# stm32hw05.net
KiCad netlist of a schematic drawn in EAGLE
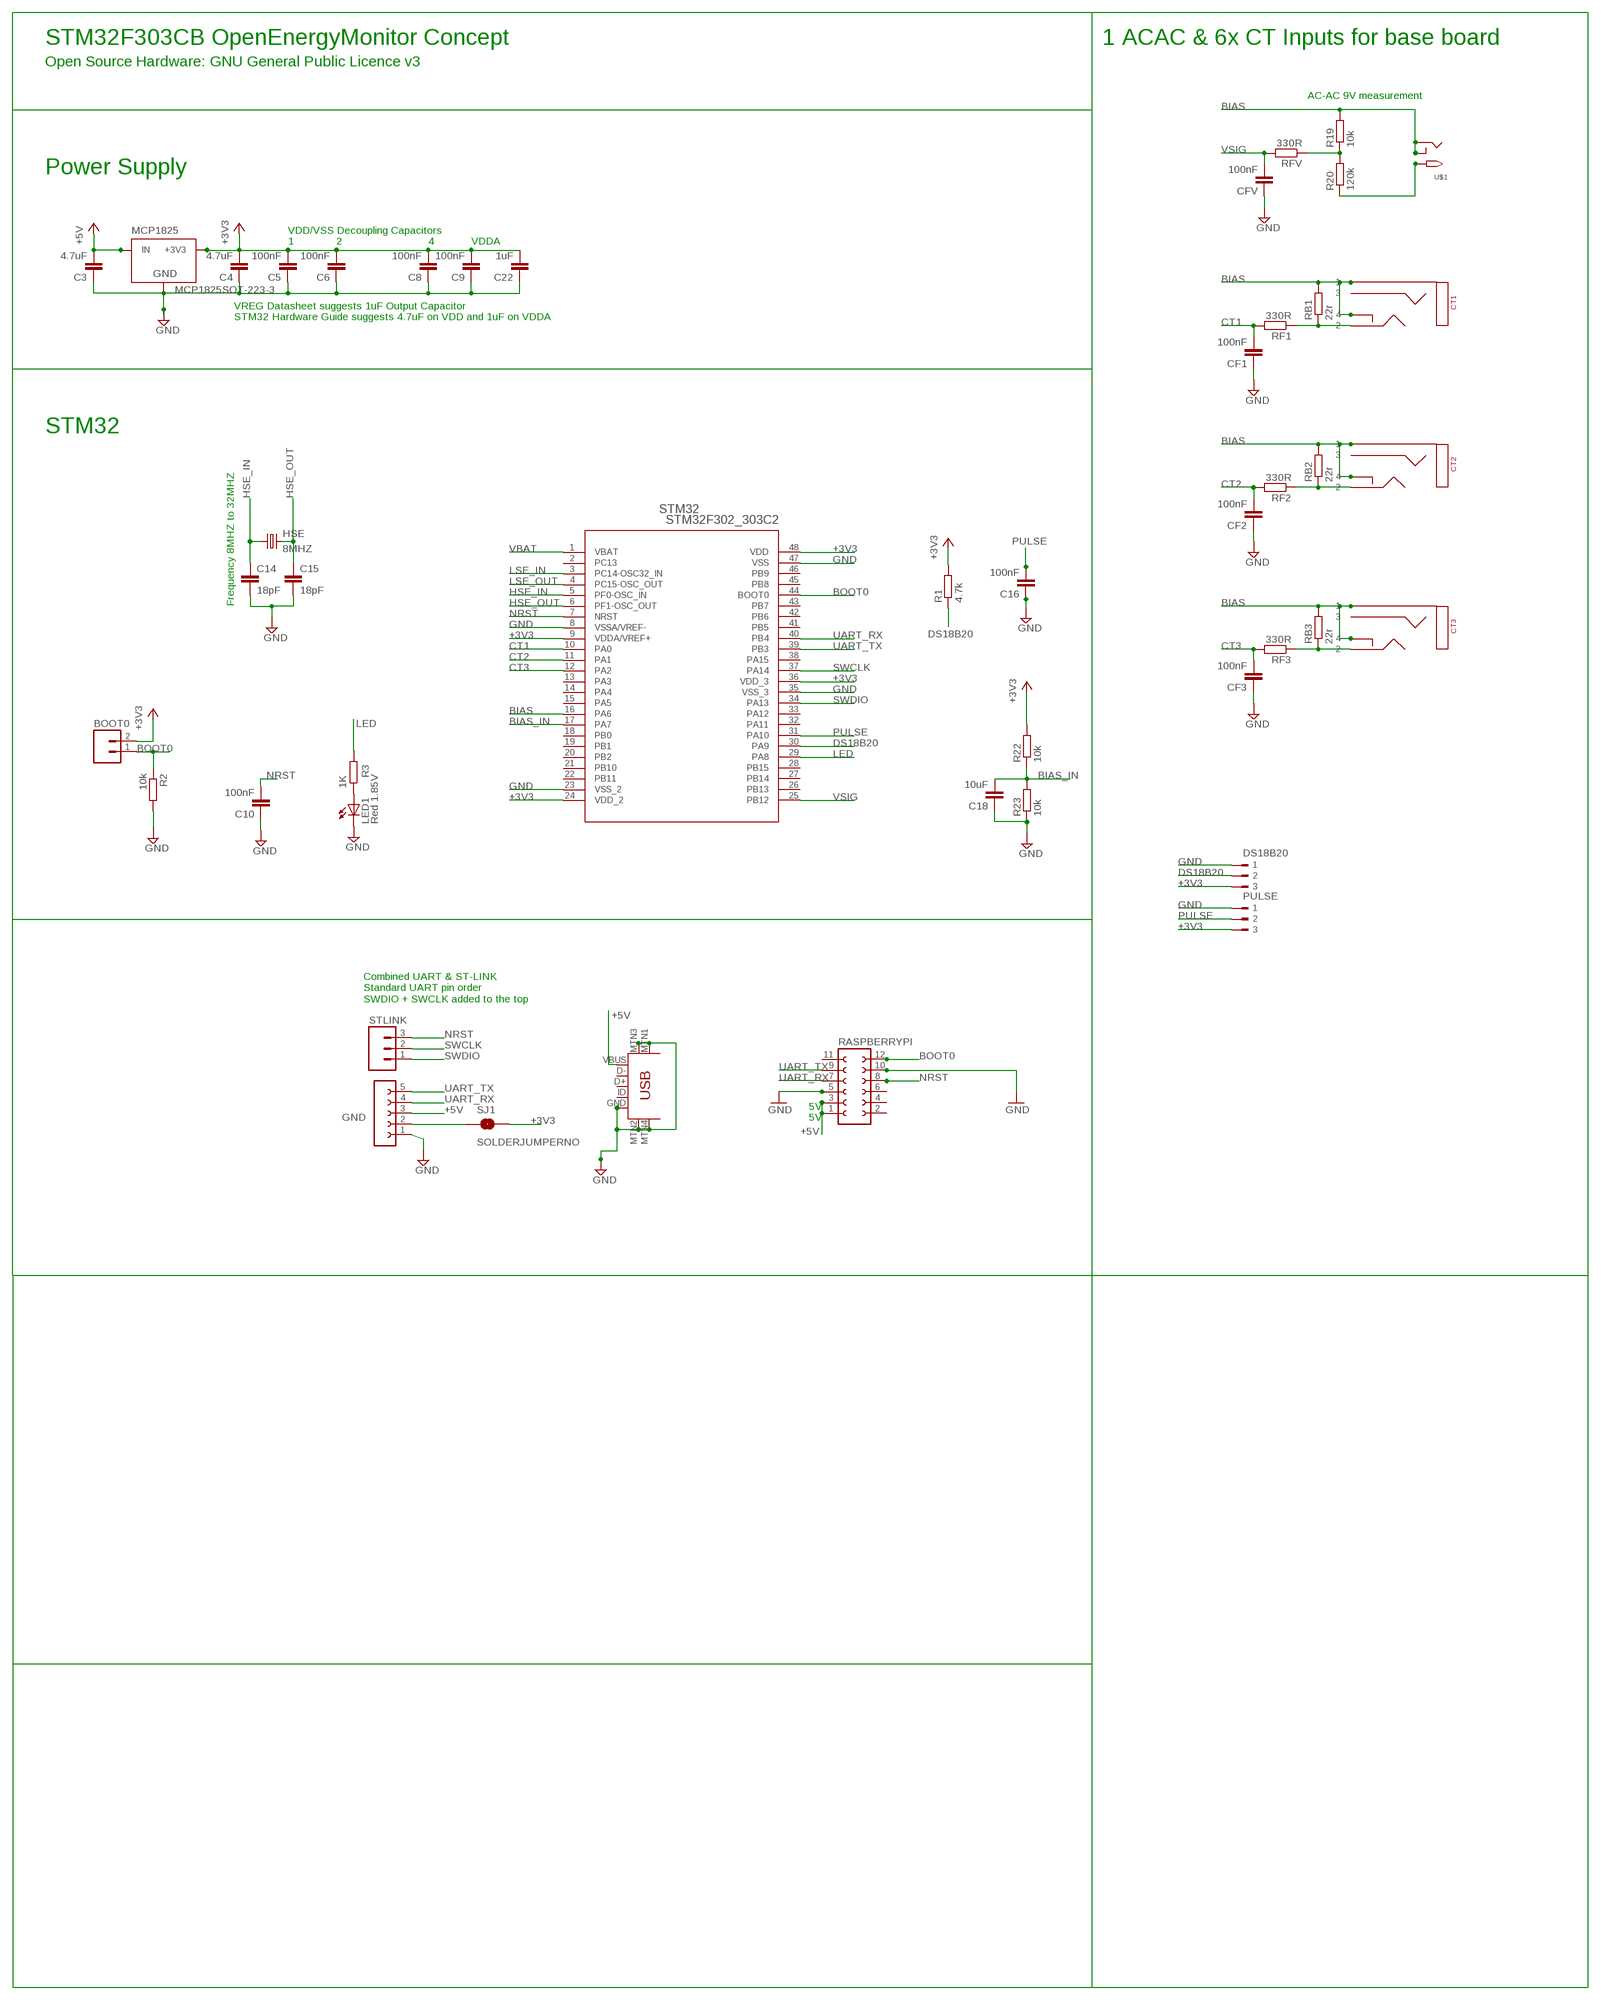
[diagram p0: schematic, sheet 1]

(export (version "E")
  (design (tool "Eeschema 10.0.6"))
  (components
    (comp (ref "BOOT0")
      (value "M02PTH")
      (footprint "eagle-import:1X02")
      (libsource (lib "eagle-import") (part "M02PTH"))
    )
    (comp (ref "C3")
      (value "4.7uF")
      (footprint "eagle-import:C0603")
      (libsource (lib "eagle-import") (part "C-EUC0603"))
    )
    (comp (ref "C4")
      (value "4.7uF")
      (footprint "eagle-import:C0603")
      (libsource (lib "eagle-import") (part "C-EUC0603"))
    )
    (comp (ref "C5")
      (value "100nF")
      (footprint "eagle-import:C0603")
      (libsource (lib "eagle-import") (part "C-EUC0603"))
    )
    (comp (ref "C6")
      (value "100nF")
      (footprint "eagle-import:C0603")
      (libsource (lib "eagle-import") (part "C-EUC0603"))
    )
    (comp (ref "C8")
      (value "100nF")
      (footprint "eagle-import:C0603")
      (libsource (lib "eagle-import") (part "C-EUC0603"))
    )
    (comp (ref "C9")
      (value "100nF")
      (footprint "eagle-import:C0603")
      (libsource (lib "eagle-import") (part "C-EUC0603"))
    )
    (comp (ref "C10")
      (value "100nF")
      (footprint "eagle-import:C0603")
      (libsource (lib "eagle-import") (part "C-EUC0603"))
    )
    (comp (ref "C14")
      (value "18pF")
      (footprint "eagle-import:C0603")
      (libsource (lib "eagle-import") (part "C-EUC0603"))
    )
    (comp (ref "C15")
      (value "18pF")
      (footprint "eagle-import:C0603")
      (libsource (lib "eagle-import") (part "C-EUC0603"))
    )
    (comp (ref "C16")
      (value "100nF")
      (footprint "eagle-import:C0603")
      (libsource (lib "eagle-import") (part "C-EUC0603"))
    )
    (comp (ref "C18")
      (value "10uF")
      (footprint "eagle-import:C0603")
      (libsource (lib "eagle-import") (part "C-EUC0603"))
    )
    (comp (ref "C22")
      (value "1uF")
      (footprint "eagle-import:C0603")
      (libsource (lib "eagle-import") (part "C-EUC0603"))
    )
    (comp (ref "CF1")
      (value "100nF")
      (footprint "eagle-import:C0603")
      (libsource (lib "eagle-import") (part "C-EUC0603"))
    )
    (comp (ref "CF2")
      (value "100nF")
      (footprint "eagle-import:C0603")
      (libsource (lib "eagle-import") (part "C-EUC0603"))
    )
    (comp (ref "CF3")
      (value "100nF")
      (footprint "eagle-import:C0603")
      (libsource (lib "eagle-import") (part "C-EUC0603"))
    )
    (comp (ref "CFV")
      (value "100nF")
      (footprint "eagle-import:C0603")
      (libsource (lib "eagle-import") (part "C-EUC0603"))
    )
    (comp (ref "CT1")
      (value "STEREO_SMD")
      (footprint "eagle-import:STEREO_SMT")
      (libsource (lib "eagle-import") (part "STEREO_SMD"))
    )
    (comp (ref "CT2")
      (value "STEREO_SMD")
      (footprint "eagle-import:STEREO_SMT")
      (libsource (lib "eagle-import") (part "STEREO_SMD"))
    )
    (comp (ref "CT3")
      (value "STEREO_SMD")
      (footprint "eagle-import:STEREO_SMT")
      (libsource (lib "eagle-import") (part "STEREO_SMD"))
    )
    (comp (ref "DS18B20")
      (value "180-3")
      (footprint "eagle-import:180-3")
      (libsource (lib "eagle-import") (part "180-3"))
    )
    (comp (ref "GND")
      (value "UART")
      (footprint "eagle-import:FE05-1")
      (libsource (lib "eagle-import") (part "FE05-1"))
    )
    (comp (ref "HSE")
      (value "8MHZ")
      (footprint "eagle-import:CTS406")
      (libsource (lib "eagle-import") (part "CRYSTALCTS406"))
    )
    (comp (ref "LED1")
      (value "Red 1.85V")
      (footprint "eagle-import:CHIP-LED0805")
      (libsource (lib "eagle-import") (part "LEDCHIP-LED0805"))
    )
    (comp (ref "MCP1825")
      (value "MCP1825SOT-223-3")
      (footprint "eagle-import:SOT-223")
      (libsource (lib "eagle-import") (part "MCP1825SOT-223-3"))
    )
    (comp (ref "PULSE")
      (value "180-3")
      (footprint "eagle-import:180-3")
      (libsource (lib "eagle-import") (part "180-3"))
    )
    (comp (ref "R1")
      (value "4.7k")
      (footprint "eagle-import:R0603")
      (libsource (lib "eagle-import") (part "resistor_R-EU_R0603"))
    )
    (comp (ref "R2")
      (value "10k")
      (footprint "eagle-import:R0603")
      (libsource (lib "eagle-import") (part "resistor_R-EU_R0603"))
    )
    (comp (ref "R3")
      (value "1K")
      (footprint "eagle-import:R0603")
      (libsource (lib "eagle-import") (part "R-EU_R0603"))
    )
    (comp (ref "R19")
      (value "10k")
      (footprint "eagle-import:R0603")
      (libsource (lib "eagle-import") (part "resistor_R-EU_R0603"))
    )
    (comp (ref "R20")
      (value "120k")
      (footprint "eagle-import:R0603")
      (libsource (lib "eagle-import") (part "resistor_R-EU_R0603"))
    )
    (comp (ref "R22")
      (value "10k")
      (footprint "eagle-import:R0603")
      (libsource (lib "eagle-import") (part "resistor_R-EU_R0603"))
    )
    (comp (ref "R23")
      (value "10k")
      (footprint "eagle-import:R0603")
      (libsource (lib "eagle-import") (part "resistor_R-EU_R0603"))
    )
    (comp (ref "RASPBERRYPI")
      (value "FE06-2")
      (footprint "eagle-import:FE06-2")
      (libsource (lib "eagle-import") (part "FE06-2"))
    )
    (comp (ref "RB1")
      (value "22r")
      (footprint "eagle-import:R0603")
      (libsource (lib "eagle-import") (part "resistor_R-EU_R0603"))
    )
    (comp (ref "RB2")
      (value "22r")
      (footprint "eagle-import:R0603")
      (libsource (lib "eagle-import") (part "resistor_R-EU_R0603"))
    )
    (comp (ref "RB3")
      (value "22r")
      (footprint "eagle-import:R0603")
      (libsource (lib "eagle-import") (part "resistor_R-EU_R0603"))
    )
    (comp (ref "RF1")
      (value "330R")
      (footprint "eagle-import:R0603")
      (libsource (lib "eagle-import") (part "resistor_R-EU_R0603"))
    )
    (comp (ref "RF2")
      (value "330R")
      (footprint "eagle-import:R0603")
      (libsource (lib "eagle-import") (part "resistor_R-EU_R0603"))
    )
    (comp (ref "RF3")
      (value "330R")
      (footprint "eagle-import:R0603")
      (libsource (lib "eagle-import") (part "resistor_R-EU_R0603"))
    )
    (comp (ref "RFV")
      (value "330R")
      (footprint "eagle-import:R0603")
      (libsource (lib "eagle-import") (part "resistor_R-EU_R0603"))
    )
    (comp (ref "SJ1")
      (value "SOLDERJUMPERNO")
      (footprint "eagle-import:SJ_2S-NO")
      (libsource (lib "eagle-import") (part "SOLDERJUMPERNO"))
    )
    (comp (ref "STLINK")
      (value "M03PTH")
      (footprint "eagle-import:1X03")
      (libsource (lib "eagle-import") (part "M03PTH"))
    )
    (comp (ref "STM32")
      (value "STM32F302_303C2")
      (footprint "eagle-import:LQFP48-7X7MM")
      (fields (field (name "MANUFACTURER_PART_NUMBER") "stm32f302_303c2"))
      (libsource (lib "eagle-import") (part "STM32F302_303C2"))
    )
    (comp (ref "U$1")
      (value "2.1MMJACKSMT")
      (footprint "eagle-import:DCJACK_2MM_SMT")
      (libsource (lib "eagle-import") (part "2.1MMJACKSMT"))
    )
    (comp (ref "U$10")
      (value "USB-MINIB-5PIN")
      (footprint "eagle-import:USB-MINIB-CISECO")
      (libsource (lib "eagle-import") (part "USB-MINIB-5PIN"))
    )
  )
  (nets
    (net (code "1") (name "+3V3") (class "Default")
      (node (ref "BOOT0") (pin "2") (pinfunction "2_2") (pintype "passive"))
      (node (ref "C22") (pin "2") (pinfunction "2_2") (pintype "passive"))
      (node (ref "C4") (pin "2") (pinfunction "2_2") (pintype "passive"))
      (node (ref "C5") (pin "2") (pinfunction "2_2") (pintype "passive"))
      (node (ref "C6") (pin "2") (pinfunction "2_2") (pintype "passive"))
      (node (ref "C8") (pin "2") (pinfunction "2_2") (pintype "passive"))
      (node (ref "C9") (pin "2") (pinfunction "2_2") (pintype "passive"))
      (node (ref "DS18B20") (pin "3") (pinfunction "3_3") (pintype "passive"))
      (node (ref "MCP1825") (pin "3") (pinfunction "+3V3_3") (pintype "power_in"))
      (node (ref "PULSE") (pin "3") (pinfunction "3_3") (pintype "passive"))
      (node (ref "R1") (pin "2") (pinfunction "2_2") (pintype "passive"))
      (node (ref "R22") (pin "2") (pinfunction "2_2") (pintype "passive"))
      (node (ref "SJ1") (pin "2") (pinfunction "2_2") (pintype "passive"))
      (node (ref "STM32") (pin "24") (pinfunction "VDD_2_24") (pintype "power_in"))
      (node (ref "STM32") (pin "36") (pinfunction "VDD_3_36") (pintype "power_in"))
      (node (ref "STM32") (pin "48") (pinfunction "VDD_48") (pintype "power_in"))
      (node (ref "STM32") (pin "9") (pinfunction "VDDA/VREF+_9") (pintype "power_in"))
    )
    (net (code "2") (name "+5V") (class "Default")
      (node (ref "C3") (pin "2") (pinfunction "2_2") (pintype "passive"))
      (node (ref "GND") (pin "3") (pinfunction "3_3") (pintype "passive"))
      (node (ref "MCP1825") (pin "1") (pinfunction "IN_1") (pintype "power_in"))
      (node (ref "RASPBERRYPI") (pin "1") (pinfunction "1_1") (pintype "passive"))
      (node (ref "RASPBERRYPI") (pin "3") (pinfunction "3_3") (pintype "passive"))
      (node (ref "U$10") (pin "VBUS") (pinfunction "VBUS_VBUS") (pintype "bidirectional"))
    )
    (net (code "3") (name "/BIAS") (class "Default")
      (node (ref "CT1") (pin "P$1") (pinfunction "1_P$1") (pintype "bidirectional"))
      (node (ref "CT1") (pin "P$4") (pinfunction "4_P$4") (pintype "bidirectional"))
      (node (ref "CT2") (pin "P$1") (pinfunction "1_P$1") (pintype "bidirectional"))
      (node (ref "CT2") (pin "P$4") (pinfunction "4_P$4") (pintype "bidirectional"))
      (node (ref "CT3") (pin "P$1") (pinfunction "1_P$1") (pintype "bidirectional"))
      (node (ref "CT3") (pin "P$4") (pinfunction "4_P$4") (pintype "bidirectional"))
      (node (ref "R19") (pin "2") (pinfunction "2_2") (pintype "passive"))
      (node (ref "RB1") (pin "2") (pinfunction "2_2") (pintype "passive"))
      (node (ref "RB2") (pin "2") (pinfunction "2_2") (pintype "passive"))
      (node (ref "RB3") (pin "2") (pinfunction "2_2") (pintype "passive"))
      (node (ref "STM32") (pin "16") (pinfunction "PA6_16") (pintype "bidirectional"))
      (node (ref "U$1") (pin "GND") (pinfunction "RING_GND") (pintype "bidirectional"))
      (node (ref "U$1") (pin "GNDBREAK") (pinfunction "RING_SW_GNDBREAK") (pintype "bidirectional"))
    )
    (net (code "4") (name "/BIAS_IN") (class "Default")
      (node (ref "C18") (pin "2") (pinfunction "2_2") (pintype "passive"))
      (node (ref "R22") (pin "1") (pinfunction "1_1") (pintype "passive"))
      (node (ref "R23") (pin "2") (pinfunction "2_2") (pintype "passive"))
      (node (ref "STM32") (pin "17") (pinfunction "PA7_17") (pintype "bidirectional"))
    )
    (net (code "5") (name "/BOOT0") (class "Default")
      (node (ref "BOOT0") (pin "1") (pinfunction "1_1") (pintype "passive"))
      (node (ref "R2") (pin "1") (pinfunction "1_1") (pintype "passive"))
      (node (ref "RASPBERRYPI") (pin "12") (pinfunction "12_12") (pintype "passive"))
      (node (ref "STM32") (pin "44") (pinfunction "BOOT0_44") (pintype "input"))
    )
    (net (code "6") (name "/CT1") (class "Default")
      (node (ref "CF1") (pin "2") (pinfunction "2_2") (pintype "passive"))
      (node (ref "RF1") (pin "2") (pinfunction "2_2") (pintype "passive"))
      (node (ref "STM32") (pin "10") (pinfunction "PA0_10") (pintype "bidirectional"))
    )
    (net (code "7") (name "/CT2") (class "Default")
      (node (ref "CF2") (pin "2") (pinfunction "2_2") (pintype "passive"))
      (node (ref "RF2") (pin "2") (pinfunction "2_2") (pintype "passive"))
      (node (ref "STM32") (pin "11") (pinfunction "PA1_11") (pintype "bidirectional"))
    )
    (net (code "8") (name "/CT3") (class "Default")
      (node (ref "CF3") (pin "2") (pinfunction "2_2") (pintype "passive"))
      (node (ref "RF3") (pin "2") (pinfunction "2_2") (pintype "passive"))
      (node (ref "STM32") (pin "12") (pinfunction "PA2_12") (pintype "bidirectional"))
    )
    (net (code "9") (name "/DS18B20") (class "Default")
      (node (ref "DS18B20") (pin "2") (pinfunction "2_2") (pintype "passive"))
      (node (ref "R1") (pin "1") (pinfunction "1_1") (pintype "passive"))
      (node (ref "STM32") (pin "30") (pinfunction "PA9_30") (pintype "bidirectional"))
    )
    (net (code "10") (name "/HSE_IN") (class "Default")
      (node (ref "C14") (pin "1") (pinfunction "1_1") (pintype "passive"))
      (node (ref "HSE") (pin "1") (pinfunction "1_1") (pintype "passive"))
      (node (ref "STM32") (pin "5") (pinfunction "PF0-OSC_IN_5") (pintype "bidirectional"))
    )
    (net (code "11") (name "/HSE_OUT") (class "Default")
      (node (ref "C15") (pin "1") (pinfunction "1_1") (pintype "passive"))
      (node (ref "HSE") (pin "3") (pinfunction "2_3") (pintype "passive"))
      (node (ref "STM32") (pin "6") (pinfunction "PF1-OSC_OUT_6") (pintype "bidirectional"))
    )
    (net (code "12") (name "/LED") (class "Default")
      (node (ref "R3") (pin "2") (pinfunction "2_2") (pintype "passive"))
      (node (ref "STM32") (pin "29") (pinfunction "PA8_29") (pintype "bidirectional"))
    )
    (net (code "13") (name "/LSE_IN") (class "Default")
      (node (ref "STM32") (pin "3") (pinfunction "PC14-OSC32_IN_3") (pintype "bidirectional"))
    )
    (net (code "14") (name "/LSE_OUT") (class "Default")
      (node (ref "STM32") (pin "4") (pinfunction "PC15-OSC_OUT_4") (pintype "bidirectional"))
    )
    (net (code "15") (name "/NRST") (class "Default")
      (node (ref "C10") (pin "2") (pinfunction "2_2") (pintype "passive"))
      (node (ref "RASPBERRYPI") (pin "8") (pinfunction "8_8") (pintype "passive"))
      (node (ref "STLINK") (pin "3") (pinfunction "3_3") (pintype "passive"))
      (node (ref "STM32") (pin "7") (pinfunction "NRST_7") (pintype "bidirectional"))
    )
    (net (code "16") (name "/PULSE") (class "Default")
      (node (ref "C16") (pin "2") (pinfunction "2_2") (pintype "passive"))
      (node (ref "PULSE") (pin "2") (pinfunction "2_2") (pintype "passive"))
      (node (ref "STM32") (pin "31") (pinfunction "PA10_31") (pintype "bidirectional"))
    )
    (net (code "17") (name "/SWCLK") (class "Default")
      (node (ref "STLINK") (pin "2") (pinfunction "2_2") (pintype "passive"))
      (node (ref "STM32") (pin "37") (pinfunction "PA14_37") (pintype "bidirectional"))
    )
    (net (code "18") (name "/SWDIO") (class "Default")
      (node (ref "STLINK") (pin "1") (pinfunction "1_1") (pintype "passive"))
      (node (ref "STM32") (pin "34") (pinfunction "PA13_34") (pintype "bidirectional"))
    )
    (net (code "19") (name "/UART_RX") (class "Default")
      (node (ref "GND") (pin "4") (pinfunction "4_4") (pintype "passive"))
      (node (ref "RASPBERRYPI") (pin "7") (pinfunction "7_7") (pintype "passive"))
      (node (ref "STM32") (pin "40") (pinfunction "PB4_40") (pintype "bidirectional"))
    )
    (net (code "20") (name "/UART_TX") (class "Default")
      (node (ref "GND") (pin "5") (pinfunction "5_5") (pintype "passive"))
      (node (ref "RASPBERRYPI") (pin "9") (pinfunction "9_9") (pintype "passive"))
      (node (ref "STM32") (pin "39") (pinfunction "PB3_39") (pintype "bidirectional"))
    )
    (net (code "21") (name "/VBAT") (class "Default")
      (node (ref "STM32") (pin "1") (pinfunction "VBAT_1") (pintype "power_in"))
    )
    (net (code "22") (name "/VSIG") (class "Default")
      (node (ref "CFV") (pin "2") (pinfunction "2_2") (pintype "passive"))
      (node (ref "RFV") (pin "2") (pinfunction "2_2") (pintype "passive"))
      (node (ref "STM32") (pin "25") (pinfunction "PB12_25") (pintype "bidirectional"))
    )
    (net (code "23") (name "GND") (class "Default")
      (node (ref "C10") (pin "1") (pinfunction "1_1") (pintype "passive"))
      (node (ref "C14") (pin "2") (pinfunction "2_2") (pintype "passive"))
      (node (ref "C15") (pin "2") (pinfunction "2_2") (pintype "passive"))
      (node (ref "C16") (pin "1") (pinfunction "1_1") (pintype "passive"))
      (node (ref "C18") (pin "1") (pinfunction "1_1") (pintype "passive"))
      (node (ref "C22") (pin "1") (pinfunction "1_1") (pintype "passive"))
      (node (ref "C3") (pin "1") (pinfunction "1_1") (pintype "passive"))
      (node (ref "C4") (pin "1") (pinfunction "1_1") (pintype "passive"))
      (node (ref "C5") (pin "1") (pinfunction "1_1") (pintype "passive"))
      (node (ref "C6") (pin "1") (pinfunction "1_1") (pintype "passive"))
      (node (ref "C8") (pin "1") (pinfunction "1_1") (pintype "passive"))
      (node (ref "C9") (pin "1") (pinfunction "1_1") (pintype "passive"))
      (node (ref "CF1") (pin "1") (pinfunction "1_1") (pintype "passive"))
      (node (ref "CF2") (pin "1") (pinfunction "1_1") (pintype "passive"))
      (node (ref "CF3") (pin "1") (pinfunction "1_1") (pintype "passive"))
      (node (ref "CFV") (pin "1") (pinfunction "1_1") (pintype "passive"))
      (node (ref "DS18B20") (pin "1") (pinfunction "1_1") (pintype "passive"))
      (node (ref "GND") (pin "1") (pinfunction "1_1") (pintype "passive"))
      (node (ref "LED1") (pin "C") (pinfunction "C_C") (pintype "passive"))
      (node (ref "MCP1825") (pin "2") (pinfunction "GND_2") (pintype "power_in"))
      (node (ref "PULSE") (pin "1") (pinfunction "1_1") (pintype "passive"))
      (node (ref "R2") (pin "2") (pinfunction "2_2") (pintype "passive"))
      (node (ref "R23") (pin "1") (pinfunction "1_1") (pintype "passive"))
      (node (ref "RASPBERRYPI") (pin "10") (pinfunction "10_10") (pintype "passive"))
      (node (ref "RASPBERRYPI") (pin "5") (pinfunction "5_5") (pintype "passive"))
      (node (ref "STM32") (pin "23") (pinfunction "VSS_2_23") (pintype "power_in"))
      (node (ref "STM32") (pin "35") (pinfunction "VSS_3_35") (pintype "power_in"))
      (node (ref "STM32") (pin "47") (pinfunction "VSS_47") (pintype "power_in"))
      (node (ref "STM32") (pin "8") (pinfunction "VSSA/VREF-_8") (pintype "power_in"))
      (node (ref "U$10") (pin "GND") (pinfunction "GND_GND") (pintype "bidirectional"))
      (node (ref "U$10") (pin "MTN1") (pinfunction "MTN2_MTN1") (pintype "bidirectional"))
      (node (ref "U$10") (pin "MTN2") (pinfunction "MTN3_MTN2") (pintype "bidirectional"))
      (node (ref "U$10") (pin "MTN3") (pinfunction "MTN1_MTN3") (pintype "bidirectional"))
      (node (ref "U$10") (pin "MTN4") (pinfunction "MTN4_MTN4") (pintype "bidirectional"))
    )
    (net (code "24") (name "Net-(CT1-2)") (class "Default")
      (node (ref "CT1") (pin "P$2") (pinfunction "2_P$2") (pintype "bidirectional"))
      (node (ref "RB1") (pin "1") (pinfunction "1_1") (pintype "passive"))
      (node (ref "RF1") (pin "1") (pinfunction "1_1") (pintype "passive"))
    )
    (net (code "25") (name "Net-(CT2-2)") (class "Default")
      (node (ref "CT2") (pin "P$2") (pinfunction "2_P$2") (pintype "bidirectional"))
      (node (ref "RB2") (pin "1") (pinfunction "1_1") (pintype "passive"))
      (node (ref "RF2") (pin "1") (pinfunction "1_1") (pintype "passive"))
    )
    (net (code "26") (name "Net-(CT3-2)") (class "Default")
      (node (ref "CT3") (pin "P$2") (pinfunction "2_P$2") (pintype "bidirectional"))
      (node (ref "RB3") (pin "1") (pinfunction "1_1") (pintype "passive"))
      (node (ref "RF3") (pin "1") (pinfunction "1_1") (pintype "passive"))
    )
    (net (code "27") (name "Net-(GND-Pad2)") (class "Default")
      (node (ref "GND") (pin "2") (pinfunction "2_2") (pintype "passive"))
      (node (ref "SJ1") (pin "1") (pinfunction "1_1") (pintype "passive"))
    )
    (net (code "28") (name "Net-(LED1-PadA)") (class "Default")
      (node (ref "LED1") (pin "A") (pinfunction "A_A") (pintype "passive"))
      (node (ref "R3") (pin "1") (pinfunction "1_1") (pintype "passive"))
    )
    (net (code "29") (name "Net-(R19-Pad1)") (class "Default")
      (node (ref "R19") (pin "1") (pinfunction "1_1") (pintype "passive"))
      (node (ref "R20") (pin "2") (pinfunction "2_2") (pintype "passive"))
      (node (ref "RFV") (pin "1") (pinfunction "1_1") (pintype "passive"))
    )
    (net (code "30") (name "Net-(U$1-TIP)") (class "Default")
      (node (ref "R20") (pin "1") (pinfunction "1_1") (pintype "passive"))
      (node (ref "U$1") (pin "PWR2") (pinfunction "TIP_PWR2") (pintype "bidirectional"))
    )
    (net (code "31") (name "unconnected-(CT1-3-PadP$3)") (class "Default")
      (node (ref "CT1") (pin "P$3") (pinfunction "3_P$3") (pintype "bidirectional"))
    )
    (net (code "32") (name "unconnected-(CT2-3-PadP$3)") (class "Default")
      (node (ref "CT2") (pin "P$3") (pinfunction "3_P$3") (pintype "bidirectional"))
    )
    (net (code "33") (name "unconnected-(CT3-3-PadP$3)") (class "Default")
      (node (ref "CT3") (pin "P$3") (pinfunction "3_P$3") (pintype "bidirectional"))
    )
    (net (code "34") (name "unconnected-(RASPBERRYPI-Pad2)") (class "Default")
      (node (ref "RASPBERRYPI") (pin "2") (pinfunction "2_2") (pintype "passive"))
    )
    (net (code "35") (name "unconnected-(RASPBERRYPI-Pad4)") (class "Default")
      (node (ref "RASPBERRYPI") (pin "4") (pinfunction "4_4") (pintype "passive"))
    )
    (net (code "36") (name "unconnected-(RASPBERRYPI-Pad6)") (class "Default")
      (node (ref "RASPBERRYPI") (pin "6") (pinfunction "6_6") (pintype "passive"))
    )
    (net (code "37") (name "unconnected-(RASPBERRYPI-Pad11)") (class "Default")
      (node (ref "RASPBERRYPI") (pin "11") (pinfunction "11_11") (pintype "passive"))
    )
    (net (code "38") (name "unconnected-(STM32-PA3-Pad13)") (class "Default")
      (node (ref "STM32") (pin "13") (pinfunction "PA3_13") (pintype "bidirectional"))
    )
    (net (code "39") (name "unconnected-(STM32-PA4-Pad14)") (class "Default")
      (node (ref "STM32") (pin "14") (pinfunction "PA4_14") (pintype "bidirectional"))
    )
    (net (code "40") (name "unconnected-(STM32-PA5-Pad15)") (class "Default")
      (node (ref "STM32") (pin "15") (pinfunction "PA5_15") (pintype "bidirectional"))
    )
    (net (code "41") (name "unconnected-(STM32-PA11-Pad32)") (class "Default")
      (node (ref "STM32") (pin "32") (pinfunction "PA11_32") (pintype "bidirectional"))
    )
    (net (code "42") (name "unconnected-(STM32-PA12-Pad33)") (class "Default")
      (node (ref "STM32") (pin "33") (pinfunction "PA12_33") (pintype "bidirectional"))
    )
    (net (code "43") (name "unconnected-(STM32-PA15-Pad38)") (class "Default")
      (node (ref "STM32") (pin "38") (pinfunction "PA15_38") (pintype "bidirectional"))
    )
    (net (code "44") (name "unconnected-(STM32-PB0-Pad18)") (class "Default")
      (node (ref "STM32") (pin "18") (pinfunction "PB0_18") (pintype "bidirectional"))
    )
    (net (code "45") (name "unconnected-(STM32-PB1-Pad19)") (class "Default")
      (node (ref "STM32") (pin "19") (pinfunction "PB1_19") (pintype "bidirectional"))
    )
    (net (code "46") (name "unconnected-(STM32-PB2-Pad20)") (class "Default")
      (node (ref "STM32") (pin "20") (pinfunction "PB2_20") (pintype "bidirectional"))
    )
    (net (code "47") (name "unconnected-(STM32-PB5-Pad41)") (class "Default")
      (node (ref "STM32") (pin "41") (pinfunction "PB5_41") (pintype "bidirectional"))
    )
    (net (code "48") (name "unconnected-(STM32-PB6-Pad42)") (class "Default")
      (node (ref "STM32") (pin "42") (pinfunction "PB6_42") (pintype "bidirectional"))
    )
    (net (code "49") (name "unconnected-(STM32-PB7-Pad43)") (class "Default")
      (node (ref "STM32") (pin "43") (pinfunction "PB7_43") (pintype "bidirectional"))
    )
    (net (code "50") (name "unconnected-(STM32-PB8-Pad45)") (class "Default")
      (node (ref "STM32") (pin "45") (pinfunction "PB8_45") (pintype "bidirectional"))
    )
    (net (code "51") (name "unconnected-(STM32-PB9-Pad46)") (class "Default")
      (node (ref "STM32") (pin "46") (pinfunction "PB9_46") (pintype "bidirectional"))
    )
    (net (code "52") (name "unconnected-(STM32-PB10-Pad21)") (class "Default")
      (node (ref "STM32") (pin "21") (pinfunction "PB10_21") (pintype "bidirectional"))
    )
    (net (code "53") (name "unconnected-(STM32-PB11-Pad22)") (class "Default")
      (node (ref "STM32") (pin "22") (pinfunction "PB11_22") (pintype "bidirectional"))
    )
    (net (code "54") (name "unconnected-(STM32-PB13-Pad26)") (class "Default")
      (node (ref "STM32") (pin "26") (pinfunction "PB13_26") (pintype "bidirectional"))
    )
    (net (code "55") (name "unconnected-(STM32-PB14-Pad27)") (class "Default")
      (node (ref "STM32") (pin "27") (pinfunction "PB14_27") (pintype "bidirectional"))
    )
    (net (code "56") (name "unconnected-(STM32-PB15-Pad28)") (class "Default")
      (node (ref "STM32") (pin "28") (pinfunction "PB15_28") (pintype "bidirectional"))
    )
    (net (code "57") (name "unconnected-(STM32-PC13-Pad2)") (class "Default")
      (node (ref "STM32") (pin "2") (pinfunction "PC13_2") (pintype "bidirectional"))
    )
    (net (code "58") (name "unconnected-(U$10-PadD+)") (class "Default")
      (node (ref "U$10") (pin "D+") (pinfunction "D+_D+") (pintype "bidirectional"))
    )
    (net (code "59") (name "unconnected-(U$10-PadD-)") (class "Default")
      (node (ref "U$10") (pin "D-") (pinfunction "D-_D-") (pintype "bidirectional"))
    )
    (net (code "60") (name "unconnected-(U$10-PadID)") (class "Default")
      (node (ref "U$10") (pin "ID") (pinfunction "ID_ID") (pintype "bidirectional"))
    )
  )
)
